# Segger_JTAG_v1p2.net
KiCad netlist of a schematic drawn in EAGLE
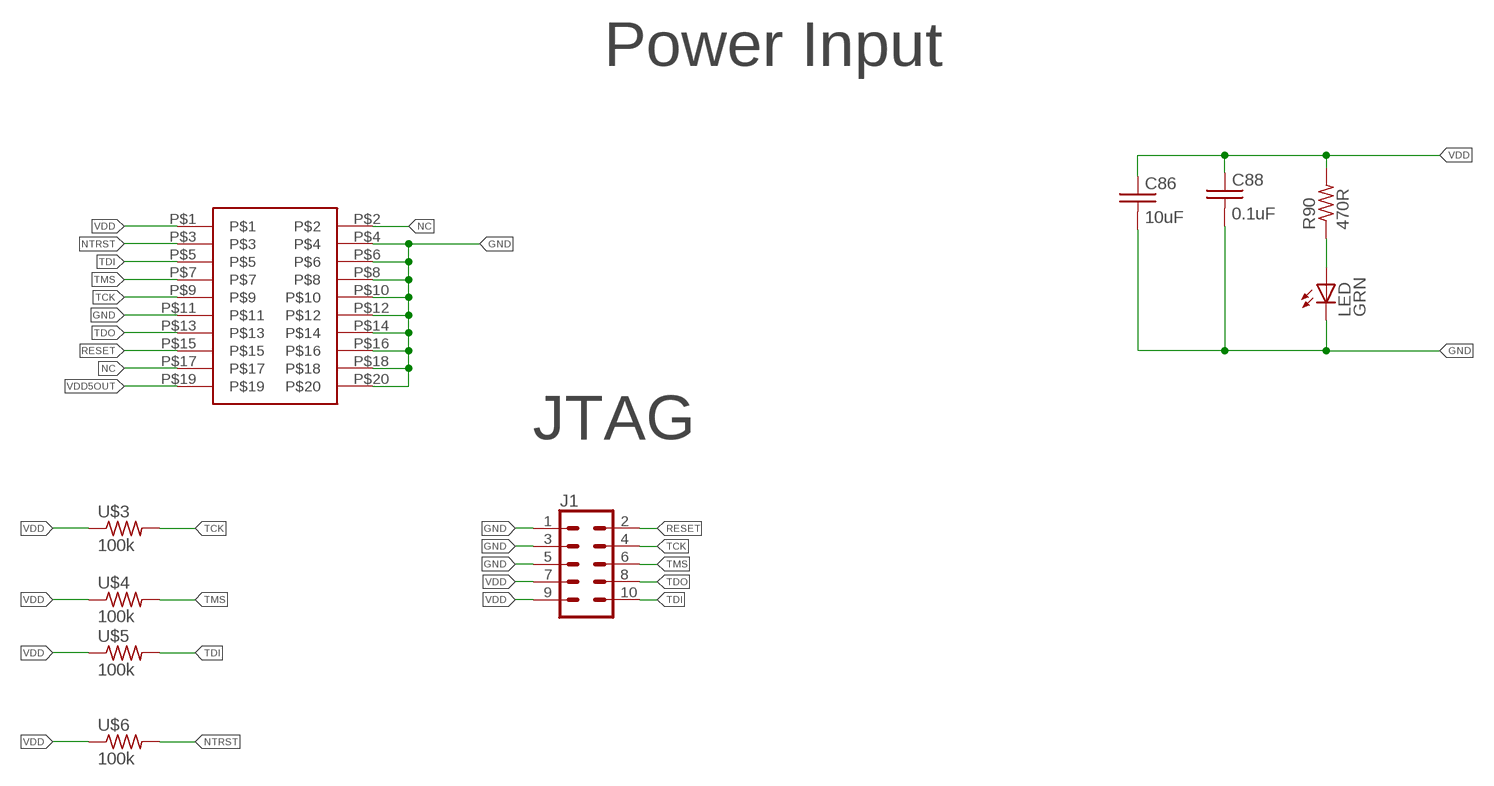
[diagram p0: schematic, sheet 1]

(export (version "E")
  (design (tool "Eeschema 10.0.6"))
  (components
    (comp (ref "C86")
      (value "10uF")
      (footprint "eagle-import:0805")
      (libsource (lib "eagle-import") (part "C_0805"))
    )
    (comp (ref "C88")
      (value "0.1uF")
      (footprint "eagle-import:0805")
      (libsource (lib "eagle-import") (part "C_0805"))
    )
    (comp (ref "J1")
      (value "CONN_05X2SHD")
      (footprint "eagle-import:2X5-SHROUDED")
      (libsource (lib "eagle-import") (part "CONN_05X2SHD"))
    )
    (comp (ref "LED")
      (value "LED_0805_GREEN")
      (footprint "eagle-import:LED_0805_GREEN")
      (libsource (lib "eagle-import") (part "LED_0805_GREEN"))
    )
    (comp (ref "R90")
      (value "470R")
      (footprint "eagle-import:0805")
      (libsource (lib "eagle-import") (part "R_0805"))
    )
    (comp (ref "U$2")
      (value "2_X_10_HEADER_GENERIC")
      (footprint "eagle-import:2_X_10_.1_INCH")
      (libsource (lib "eagle-import") (part "2_X_10_HEADER_GENERIC"))
    )
    (comp (ref "U$3")
      (value "100k")
      (footprint "eagle-import:0805")
      (libsource (lib "eagle-import") (part "R_0805"))
    )
    (comp (ref "U$4")
      (value "100k")
      (footprint "eagle-import:0805")
      (libsource (lib "eagle-import") (part "R_0805"))
    )
    (comp (ref "U$5")
      (value "100k")
      (footprint "eagle-import:0805")
      (libsource (lib "eagle-import") (part "R_0805"))
    )
    (comp (ref "U$6")
      (value "100k")
      (footprint "eagle-import:0805")
      (libsource (lib "eagle-import") (part "R_0805"))
    )
  )
  (nets
    (net (code "1") (name "GND") (class "Default")
      (node (ref "C86") (pin "2") (pinfunction "2_2") (pintype "passive"))
      (node (ref "C88") (pin "2") (pinfunction "2_2") (pintype "passive"))
      (node (ref "J1") (pin "1") (pinfunction "1_1") (pintype "passive"))
      (node (ref "J1") (pin "3") (pinfunction "3_3") (pintype "passive"))
      (node (ref "J1") (pin "5") (pinfunction "5_5") (pintype "passive"))
      (node (ref "LED") (pin "C") (pinfunction "C_C") (pintype "passive"))
      (node (ref "U$2") (pin "P$10") (pinfunction "P$10_P$10") (pintype "bidirectional"))
      (node (ref "U$2") (pin "P$11") (pinfunction "P$11_P$11") (pintype "bidirectional"))
      (node (ref "U$2") (pin "P$12") (pinfunction "P$12_P$12") (pintype "bidirectional"))
      (node (ref "U$2") (pin "P$14") (pinfunction "P$14_P$14") (pintype "bidirectional"))
      (node (ref "U$2") (pin "P$16") (pinfunction "P$16_P$16") (pintype "bidirectional"))
      (node (ref "U$2") (pin "P$18") (pinfunction "P$18_P$18") (pintype "bidirectional"))
      (node (ref "U$2") (pin "P$20") (pinfunction "P$20_P$20") (pintype "bidirectional"))
      (node (ref "U$2") (pin "P$4") (pinfunction "P$4_P$4") (pintype "bidirectional"))
      (node (ref "U$2") (pin "P$6") (pinfunction "P$6_P$6") (pintype "bidirectional"))
      (node (ref "U$2") (pin "P$8") (pinfunction "P$8_P$8") (pintype "bidirectional"))
    )
    (net (code "2") (name "NC") (class "Default")
      (node (ref "U$2") (pin "P$17") (pinfunction "P$17_P$17") (pintype "bidirectional"))
      (node (ref "U$2") (pin "P$2") (pinfunction "P$2_P$2") (pintype "bidirectional"))
    )
    (net (code "3") (name "NTRST") (class "Default")
      (node (ref "U$2") (pin "P$3") (pinfunction "P$3_P$3") (pintype "bidirectional"))
      (node (ref "U$6") (pin "2") (pinfunction "2_2") (pintype "passive"))
    )
    (net (code "4") (name "Net-(LED-PadA)") (class "Default")
      (node (ref "LED") (pin "A") (pinfunction "A_A") (pintype "passive"))
      (node (ref "R90") (pin "1") (pinfunction "1_1") (pintype "passive"))
    )
    (net (code "5") (name "RESET") (class "Default")
      (node (ref "J1") (pin "2") (pinfunction "2_2") (pintype "passive"))
      (node (ref "U$2") (pin "P$15") (pinfunction "P$15_P$15") (pintype "bidirectional"))
    )
    (net (code "6") (name "TCK") (class "Default")
      (node (ref "J1") (pin "4") (pinfunction "4_4") (pintype "passive"))
      (node (ref "U$2") (pin "P$9") (pinfunction "P$9_P$9") (pintype "bidirectional"))
      (node (ref "U$3") (pin "2") (pinfunction "2_2") (pintype "passive"))
    )
    (net (code "7") (name "TDI") (class "Default")
      (node (ref "J1") (pin "10") (pinfunction "10_10") (pintype "passive"))
      (node (ref "U$2") (pin "P$5") (pinfunction "P$5_P$5") (pintype "bidirectional"))
      (node (ref "U$5") (pin "2") (pinfunction "2_2") (pintype "passive"))
    )
    (net (code "8") (name "TDO") (class "Default")
      (node (ref "J1") (pin "8") (pinfunction "8_8") (pintype "passive"))
      (node (ref "U$2") (pin "P$13") (pinfunction "P$13_P$13") (pintype "bidirectional"))
    )
    (net (code "9") (name "TMS") (class "Default")
      (node (ref "J1") (pin "6") (pinfunction "6_6") (pintype "passive"))
      (node (ref "U$2") (pin "P$7") (pinfunction "P$7_P$7") (pintype "bidirectional"))
      (node (ref "U$4") (pin "2") (pinfunction "2_2") (pintype "passive"))
    )
    (net (code "10") (name "VDD") (class "Default")
      (node (ref "C86") (pin "1") (pinfunction "1_1") (pintype "passive"))
      (node (ref "C88") (pin "1") (pinfunction "1_1") (pintype "passive"))
      (node (ref "J1") (pin "7") (pinfunction "7_7") (pintype "passive"))
      (node (ref "J1") (pin "9") (pinfunction "9_9") (pintype "passive"))
      (node (ref "R90") (pin "2") (pinfunction "2_2") (pintype "passive"))
      (node (ref "U$2") (pin "P$1") (pinfunction "P$1_P$1") (pintype "bidirectional"))
      (node (ref "U$3") (pin "1") (pinfunction "1_1") (pintype "passive"))
      (node (ref "U$4") (pin "1") (pinfunction "1_1") (pintype "passive"))
      (node (ref "U$5") (pin "1") (pinfunction "1_1") (pintype "passive"))
      (node (ref "U$6") (pin "1") (pinfunction "1_1") (pintype "passive"))
    )
    (net (code "11") (name "VDD5OUT") (class "Default")
      (node (ref "U$2") (pin "P$19") (pinfunction "P$19_P$19") (pintype "bidirectional"))
    )
  )
)
